# Temporary_Solution_v2.net
KiCad netlist of a schematic drawn in EAGLE
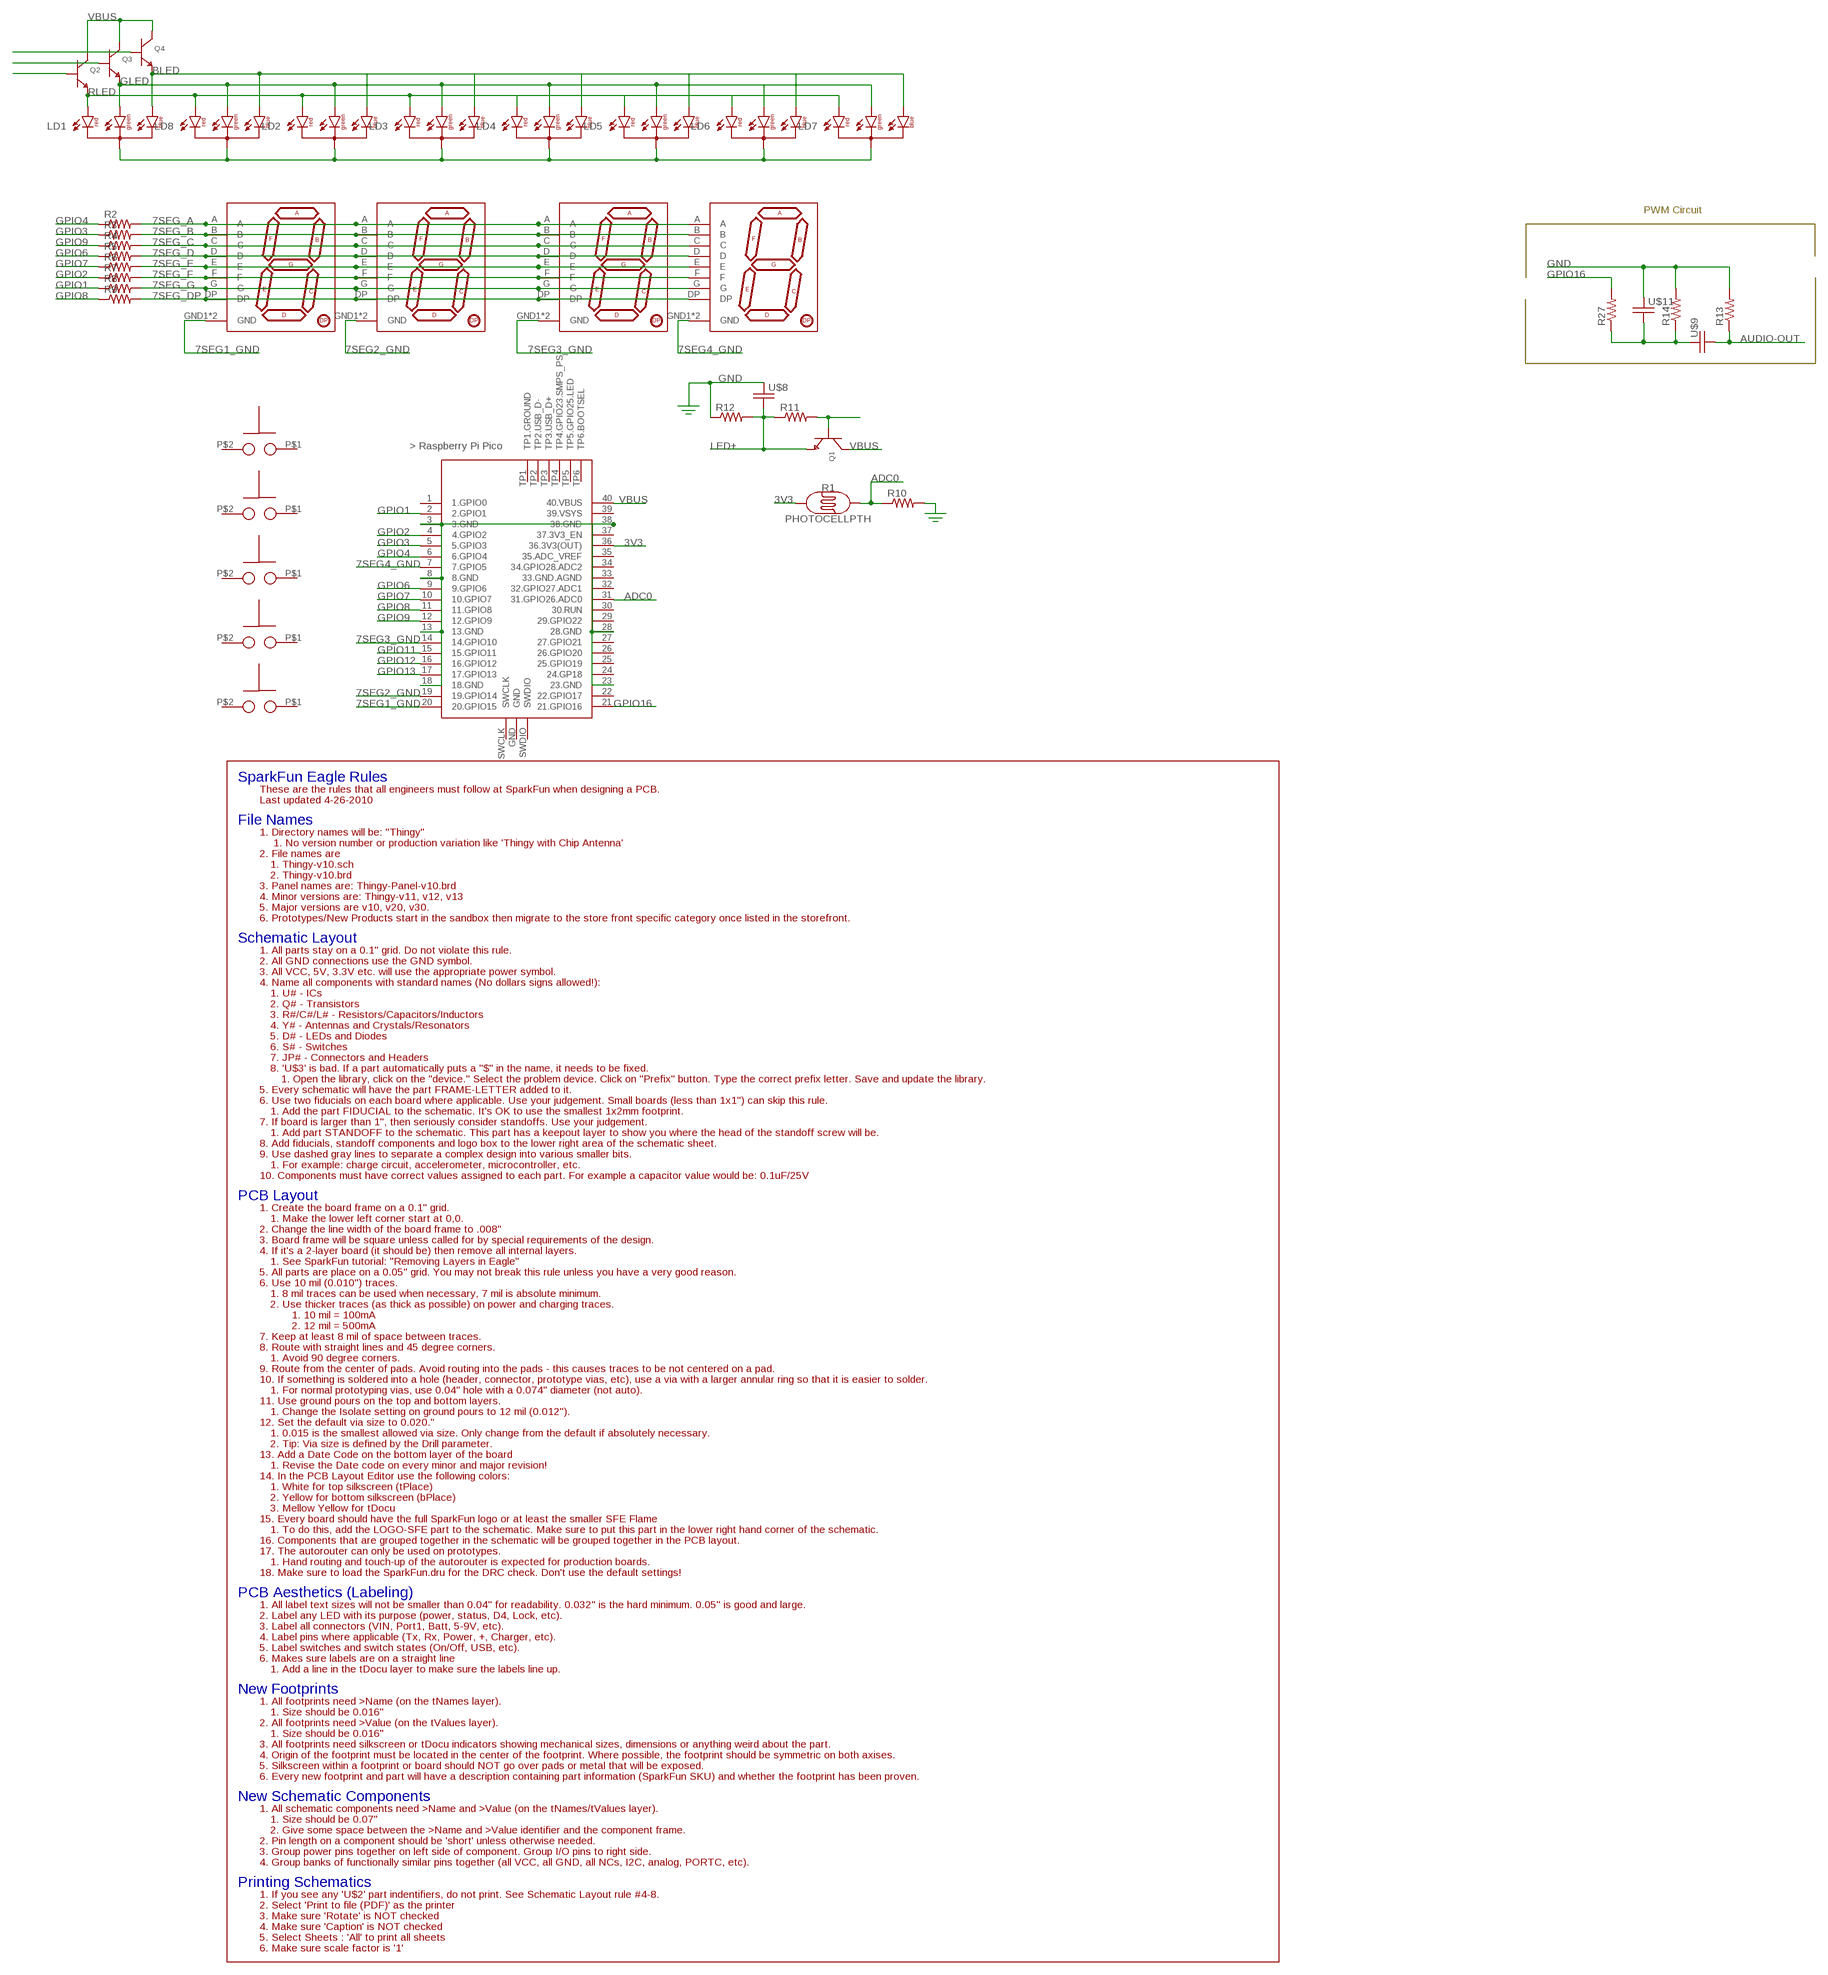
[diagram p0: schematic, sheet 1]

(export (version "E")
  (design (tool "Eeschema 10.0.6"))
  (components
    (comp (ref "D1")
      (value "7SEGMENT-1DIGIT")
      (footprint "eagle-import:7SEGMENT-1DIGIT")
      (libsource (lib "eagle-import") (part "7SEGMENT-1DIGIT"))
    )
    (comp (ref "D2")
      (value "7SEGMENT-1DIGIT")
      (footprint "eagle-import:7SEGMENT-1DIGIT")
      (libsource (lib "eagle-import") (part "7SEGMENT-1DIGIT"))
    )
    (comp (ref "D3")
      (value "7SEGMENT-1DIGIT")
      (footprint "eagle-import:7SEGMENT-1DIGIT")
      (libsource (lib "eagle-import") (part "7SEGMENT-1DIGIT"))
    )
    (comp (ref "D4")
      (value "7SEGMENT-1DIGIT")
      (footprint "eagle-import:7SEGMENT-1DIGIT")
      (libsource (lib "eagle-import") (part "7SEGMENT-1DIGIT"))
    )
    (comp (ref "LD1")
      (value "LED_RGB")
      (footprint "eagle-import:LED_RGB")
      (libsource (lib "eagle-import") (part "LED_RGB"))
    )
    (comp (ref "LD2")
      (value "LED_RGB")
      (footprint "eagle-import:LED_RGB")
      (libsource (lib "eagle-import") (part "LED_RGB"))
    )
    (comp (ref "LD3")
      (value "LED_RGB")
      (footprint "eagle-import:LED_RGB")
      (libsource (lib "eagle-import") (part "LED_RGB"))
    )
    (comp (ref "LD4")
      (value "LED_RGB")
      (footprint "eagle-import:LED_RGB")
      (libsource (lib "eagle-import") (part "LED_RGB"))
    )
    (comp (ref "LD5")
      (value "LED_RGB")
      (footprint "eagle-import:LED_RGB")
      (libsource (lib "eagle-import") (part "LED_RGB"))
    )
    (comp (ref "LD6")
      (value "LED_RGB")
      (footprint "eagle-import:LED_RGB")
      (libsource (lib "eagle-import") (part "LED_RGB"))
    )
    (comp (ref "LD7")
      (value "LED_RGB")
      (footprint "eagle-import:LED_RGB")
      (libsource (lib "eagle-import") (part "LED_RGB"))
    )
    (comp (ref "LD8")
      (value "LED_RGB")
      (footprint "eagle-import:LED_RGB")
      (libsource (lib "eagle-import") (part "LED_RGB"))
    )
    (comp (ref "Q1")
      (value "BJT_NPN_EBC_2N2222")
      (footprint "eagle-import:NPN_EBC_.1IN")
      (libsource (lib "eagle-import") (part "BJT_NPN_EBC_2N2222"))
    )
    (comp (ref "Q2")
      (value "BJT_NPN_EBC_2N2222")
      (footprint "eagle-import:NPN_EBC_.1IN")
      (libsource (lib "eagle-import") (part "BJT_NPN_EBC_2N2222"))
    )
    (comp (ref "Q3")
      (value "BJT_NPN_EBC_2N2222")
      (footprint "eagle-import:NPN_EBC_.1IN")
      (libsource (lib "eagle-import") (part "BJT_NPN_EBC_2N2222"))
    )
    (comp (ref "Q4")
      (value "BJT_NPN_EBC_2N2222")
      (footprint "eagle-import:NPN_EBC_.1IN")
      (libsource (lib "eagle-import") (part "BJT_NPN_EBC_2N2222"))
    )
    (comp (ref "R1")
      (value "PHOTOCELLPTH")
      (footprint "eagle-import:PHOTOCELL")
      (libsource (lib "eagle-import") (part "PHOTOCELLPTH"))
    )
    (comp (ref "R2")
      (value "R-US_0207/7")
      (footprint "eagle-import:0207_7")
      (libsource (lib "eagle-import") (part "R-US_0207/7"))
    )
    (comp (ref "R3")
      (value "R-US_0207/7")
      (footprint "eagle-import:0207_7")
      (libsource (lib "eagle-import") (part "R-US_0207/7"))
    )
    (comp (ref "R4")
      (value "R-US_0207/7")
      (footprint "eagle-import:0207_7")
      (libsource (lib "eagle-import") (part "R-US_0207/7"))
    )
    (comp (ref "R5")
      (value "R-US_0207/7")
      (footprint "eagle-import:0207_7")
      (libsource (lib "eagle-import") (part "R-US_0207/7"))
    )
    (comp (ref "R6")
      (value "R-US_0207/7")
      (footprint "eagle-import:0207_7")
      (libsource (lib "eagle-import") (part "R-US_0207/7"))
    )
    (comp (ref "R7")
      (value "R-US_0207/7")
      (footprint "eagle-import:0207_7")
      (libsource (lib "eagle-import") (part "R-US_0207/7"))
    )
    (comp (ref "R8")
      (value "R-US_0207/7")
      (footprint "eagle-import:0207_7")
      (libsource (lib "eagle-import") (part "R-US_0207/7"))
    )
    (comp (ref "R9")
      (value "R-US_0207/7")
      (footprint "eagle-import:0207_7")
      (libsource (lib "eagle-import") (part "R-US_0207/7"))
    )
    (comp (ref "R10")
      (value "R-US_0207/7")
      (footprint "eagle-import:0207_7")
      (libsource (lib "eagle-import") (part "R-US_0207/7"))
    )
    (comp (ref "R11")
      (value "R-US_0207/7")
      (footprint "eagle-import:0207_7")
      (libsource (lib "eagle-import") (part "R-US_0207/7"))
    )
    (comp (ref "R12")
      (value "R-US_0207/7")
      (footprint "eagle-import:0207_7")
      (libsource (lib "eagle-import") (part "R-US_0207/7"))
    )
    (comp (ref "R13")
      (value "R-US_0207/7")
      (footprint "eagle-import:0207_7")
      (libsource (lib "eagle-import") (part "R-US_0207/7"))
    )
    (comp (ref "R14")
      (value "R-US_0207/7")
      (footprint "eagle-import:0207_7")
      (libsource (lib "eagle-import") (part "R-US_0207/7"))
    )
    (comp (ref "R27")
      (value "R-US_0207/7")
      (footprint "eagle-import:0207_7")
      (libsource (lib "eagle-import") (part "R-US_0207/7"))
    )
    (comp (ref "U$2")
      (value "RASPBERRY_PI_PICO_TH")
      (footprint "eagle-import:RASPBERRY_PI_PICO_TH")
      (libsource (lib "eagle-import") (part "RASPBERRY_PI_PICO_TH"))
    )
    (comp (ref "U$3")
      (value "BUTTONPUSHBUTTON_2-PIN")
      (footprint "eagle-import:BUTTON_PUSHBUTTON_2-PIN")
      (libsource (lib "eagle-import") (part "BUTTONPUSHBUTTON_2-PIN"))
    )
    (comp (ref "U$4")
      (value "BUTTONPUSHBUTTON_2-PIN")
      (footprint "eagle-import:BUTTON_PUSHBUTTON_2-PIN")
      (libsource (lib "eagle-import") (part "BUTTONPUSHBUTTON_2-PIN"))
    )
    (comp (ref "U$5")
      (value "BUTTONPUSHBUTTON_2-PIN")
      (footprint "eagle-import:BUTTON_PUSHBUTTON_2-PIN")
      (libsource (lib "eagle-import") (part "BUTTONPUSHBUTTON_2-PIN"))
    )
    (comp (ref "U$6")
      (value "BUTTONPUSHBUTTON_2-PIN")
      (footprint "eagle-import:BUTTON_PUSHBUTTON_2-PIN")
      (libsource (lib "eagle-import") (part "BUTTONPUSHBUTTON_2-PIN"))
    )
    (comp (ref "U$7")
      (value "BUTTONPUSHBUTTON_2-PIN")
      (footprint "eagle-import:BUTTON_PUSHBUTTON_2-PIN")
      (libsource (lib "eagle-import") (part "BUTTONPUSHBUTTON_2-PIN"))
    )
    (comp (ref "U$8")
      (value "CAPACITOR-NONPOLARIZEDTH-CERAMIC")
      (footprint "eagle-import:CAPACITOR-CERAMIC")
      (libsource (lib "eagle-import") (part "CAPACITOR-NONPOLARIZEDTH-CERAMIC"))
    )
    (comp (ref "U$9")
      (value "CAPACITOR-NONPOLARIZEDTH-CERAMIC")
      (footprint "eagle-import:CAPACITOR-CERAMIC")
      (libsource (lib "eagle-import") (part "CAPACITOR-NONPOLARIZEDTH-CERAMIC"))
    )
    (comp (ref "U$11")
      (value "CAPACITOR-NONPOLARIZEDTH-CERAMIC")
      (footprint "eagle-import:CAPACITOR-CERAMIC")
      (libsource (lib "eagle-import") (part "CAPACITOR-NONPOLARIZEDTH-CERAMIC"))
    )
  )
  (nets
    (net (code "1") (name "/3V3") (class "Default")
      (node (ref "R1") (pin "1") (pinfunction "P$1_1") (pintype "bidirectional"))
      (node (ref "U$2") (pin "36") (pinfunction "36.3V3(OUT)_36") (pintype "bidirectional"))
    )
    (net (code "2") (name "/7SEG1_GND") (class "Default")
      (node (ref "D1") (pin "GND1") (pinfunction "GND_GND1") (pintype "bidirectional"))
      (node (ref "D1") (pin "GND2") (pinfunction "GND_GND2") (pintype "bidirectional"))
      (node (ref "U$2") (pin "20") (pinfunction "20.GPIO15_20") (pintype "bidirectional"))
    )
    (net (code "3") (name "/7SEG2_GND") (class "Default")
      (node (ref "D2") (pin "GND1") (pinfunction "GND_GND1") (pintype "bidirectional"))
      (node (ref "D2") (pin "GND2") (pinfunction "GND_GND2") (pintype "bidirectional"))
      (node (ref "U$2") (pin "19") (pinfunction "19.GPIO14_19") (pintype "bidirectional"))
    )
    (net (code "4") (name "/7SEG3_GND") (class "Default")
      (node (ref "D3") (pin "GND1") (pinfunction "GND_GND1") (pintype "bidirectional"))
      (node (ref "D3") (pin "GND2") (pinfunction "GND_GND2") (pintype "bidirectional"))
      (node (ref "U$2") (pin "14") (pinfunction "14.GPIO10_14") (pintype "bidirectional"))
    )
    (net (code "5") (name "/7SEG4_GND") (class "Default")
      (node (ref "D4") (pin "GND1") (pinfunction "GND_GND1") (pintype "bidirectional"))
      (node (ref "D4") (pin "GND2") (pinfunction "GND_GND2") (pintype "bidirectional"))
      (node (ref "U$2") (pin "7") (pinfunction "7.GPIO5_7") (pintype "bidirectional"))
    )
    (net (code "6") (name "/7SEG_A") (class "Default")
      (node (ref "D1") (pin "A") (pinfunction "A_A") (pintype "bidirectional"))
      (node (ref "D2") (pin "A") (pinfunction "A_A") (pintype "bidirectional"))
      (node (ref "D3") (pin "A") (pinfunction "A_A") (pintype "bidirectional"))
      (node (ref "D4") (pin "A") (pinfunction "A_A") (pintype "bidirectional"))
      (node (ref "R2") (pin "2") (pinfunction "2_2") (pintype "passive"))
    )
    (net (code "7") (name "/7SEG_B") (class "Default")
      (node (ref "D1") (pin "B") (pinfunction "B_B") (pintype "bidirectional"))
      (node (ref "D2") (pin "B") (pinfunction "B_B") (pintype "bidirectional"))
      (node (ref "D3") (pin "B") (pinfunction "B_B") (pintype "bidirectional"))
      (node (ref "D4") (pin "B") (pinfunction "B_B") (pintype "bidirectional"))
      (node (ref "R3") (pin "2") (pinfunction "2_2") (pintype "passive"))
    )
    (net (code "8") (name "/7SEG_C") (class "Default")
      (node (ref "D1") (pin "C") (pinfunction "C_C") (pintype "bidirectional"))
      (node (ref "D2") (pin "C") (pinfunction "C_C") (pintype "bidirectional"))
      (node (ref "D3") (pin "C") (pinfunction "C_C") (pintype "bidirectional"))
      (node (ref "D4") (pin "C") (pinfunction "C_C") (pintype "bidirectional"))
      (node (ref "R4") (pin "2") (pinfunction "2_2") (pintype "passive"))
    )
    (net (code "9") (name "/7SEG_D") (class "Default")
      (node (ref "D1") (pin "D") (pinfunction "D_D") (pintype "bidirectional"))
      (node (ref "D2") (pin "D") (pinfunction "D_D") (pintype "bidirectional"))
      (node (ref "D3") (pin "D") (pinfunction "D_D") (pintype "bidirectional"))
      (node (ref "D4") (pin "D") (pinfunction "D_D") (pintype "bidirectional"))
      (node (ref "R5") (pin "2") (pinfunction "2_2") (pintype "passive"))
    )
    (net (code "10") (name "/7SEG_DP") (class "Default")
      (node (ref "D1") (pin "DP") (pinfunction "DP_DP") (pintype "bidirectional"))
      (node (ref "D2") (pin "DP") (pinfunction "DP_DP") (pintype "bidirectional"))
      (node (ref "D3") (pin "DP") (pinfunction "DP_DP") (pintype "bidirectional"))
      (node (ref "D4") (pin "DP") (pinfunction "DP_DP") (pintype "bidirectional"))
      (node (ref "R9") (pin "2") (pinfunction "2_2") (pintype "passive"))
    )
    (net (code "11") (name "/7SEG_E") (class "Default")
      (node (ref "D1") (pin "E") (pinfunction "E_E") (pintype "bidirectional"))
      (node (ref "D2") (pin "E") (pinfunction "E_E") (pintype "bidirectional"))
      (node (ref "D3") (pin "E") (pinfunction "E_E") (pintype "bidirectional"))
      (node (ref "D4") (pin "E") (pinfunction "E_E") (pintype "bidirectional"))
      (node (ref "R6") (pin "2") (pinfunction "2_2") (pintype "passive"))
    )
    (net (code "12") (name "/7SEG_F") (class "Default")
      (node (ref "D1") (pin "F") (pinfunction "F_F") (pintype "bidirectional"))
      (node (ref "D2") (pin "F") (pinfunction "F_F") (pintype "bidirectional"))
      (node (ref "D3") (pin "F") (pinfunction "F_F") (pintype "bidirectional"))
      (node (ref "D4") (pin "F") (pinfunction "F_F") (pintype "bidirectional"))
      (node (ref "R7") (pin "2") (pinfunction "2_2") (pintype "passive"))
    )
    (net (code "13") (name "/7SEG_G") (class "Default")
      (node (ref "D1") (pin "G") (pinfunction "G_G") (pintype "bidirectional"))
      (node (ref "D2") (pin "G") (pinfunction "G_G") (pintype "bidirectional"))
      (node (ref "D3") (pin "G") (pinfunction "G_G") (pintype "bidirectional"))
      (node (ref "D4") (pin "G") (pinfunction "G_G") (pintype "bidirectional"))
      (node (ref "R8") (pin "2") (pinfunction "2_2") (pintype "passive"))
    )
    (net (code "14") (name "/ADC0") (class "Default")
      (node (ref "R1") (pin "2") (pinfunction "P$2_2") (pintype "bidirectional"))
      (node (ref "R10") (pin "1") (pinfunction "1_1") (pintype "passive"))
      (node (ref "U$2") (pin "31") (pinfunction "31.GPIO26.ADC0_31") (pintype "bidirectional"))
    )
    (net (code "15") (name "/AUDIO-OUT") (class "Default")
      (node (ref "R13") (pin "1") (pinfunction "1_1") (pintype "passive"))
      (node (ref "U$9") (pin "2") (pinfunction "2_2") (pintype "passive"))
    )
    (net (code "16") (name "/BLED") (class "Default")
      (node (ref "LD1") (pin "BLUE") (pinfunction "BLUE_BLUE") (pintype "passive"))
      (node (ref "LD2") (pin "BLUE") (pinfunction "BLUE_BLUE") (pintype "passive"))
      (node (ref "LD3") (pin "BLUE") (pinfunction "BLUE_BLUE") (pintype "passive"))
      (node (ref "LD4") (pin "BLUE") (pinfunction "BLUE_BLUE") (pintype "passive"))
      (node (ref "LD5") (pin "BLUE") (pinfunction "BLUE_BLUE") (pintype "passive"))
      (node (ref "LD6") (pin "BLUE") (pinfunction "BLUE_BLUE") (pintype "passive"))
      (node (ref "LD7") (pin "BLUE") (pinfunction "BLUE_BLUE") (pintype "passive"))
      (node (ref "LD8") (pin "BLUE") (pinfunction "BLUE_BLUE") (pintype "passive"))
      (node (ref "Q4") (pin "3") (pinfunction "E_3") (pintype "bidirectional"))
    )
    (net (code "17") (name "/GLED") (class "Default")
      (node (ref "LD1") (pin "GRN") (pinfunction "GREEN_GRN") (pintype "passive"))
      (node (ref "LD2") (pin "GRN") (pinfunction "GREEN_GRN") (pintype "passive"))
      (node (ref "LD3") (pin "GRN") (pinfunction "GREEN_GRN") (pintype "passive"))
      (node (ref "LD4") (pin "GRN") (pinfunction "GREEN_GRN") (pintype "passive"))
      (node (ref "LD5") (pin "GRN") (pinfunction "GREEN_GRN") (pintype "passive"))
      (node (ref "LD6") (pin "GRN") (pinfunction "GREEN_GRN") (pintype "passive"))
      (node (ref "LD7") (pin "GRN") (pinfunction "GREEN_GRN") (pintype "passive"))
      (node (ref "LD8") (pin "GRN") (pinfunction "GREEN_GRN") (pintype "passive"))
      (node (ref "Q3") (pin "3") (pinfunction "E_3") (pintype "bidirectional"))
    )
    (net (code "18") (name "/GND") (class "Default")
      (node (ref "R10") (pin "2") (pinfunction "2_2") (pintype "passive"))
      (node (ref "R12") (pin "1") (pinfunction "1_1") (pintype "passive"))
      (node (ref "R13") (pin "2") (pinfunction "2_2") (pintype "passive"))
      (node (ref "R14") (pin "2") (pinfunction "2_2") (pintype "passive"))
      (node (ref "U$11") (pin "1") (pinfunction "1_1") (pintype "passive"))
      (node (ref "U$2") (pin "13") (pinfunction "13.GND_13") (pintype "bidirectional"))
      (node (ref "U$2") (pin "18") (pinfunction "18.GND_18") (pintype "bidirectional"))
      (node (ref "U$2") (pin "23") (pinfunction "23.GND_23") (pintype "bidirectional"))
      (node (ref "U$2") (pin "28") (pinfunction "28.GND_28") (pintype "bidirectional"))
      (node (ref "U$2") (pin "3") (pinfunction "3.GND_3") (pintype "bidirectional"))
      (node (ref "U$2") (pin "38") (pinfunction "38.GND_38") (pintype "bidirectional"))
      (node (ref "U$2") (pin "8") (pinfunction "8.GND_8") (pintype "bidirectional"))
      (node (ref "U$8") (pin "1") (pinfunction "1_1") (pintype "passive"))
    )
    (net (code "19") (name "/GPIO1") (class "Default")
      (node (ref "R8") (pin "1") (pinfunction "1_1") (pintype "passive"))
      (node (ref "U$2") (pin "2") (pinfunction "2.GPIO1_2") (pintype "bidirectional"))
    )
    (net (code "20") (name "/GPIO2") (class "Default")
      (node (ref "R7") (pin "1") (pinfunction "1_1") (pintype "passive"))
      (node (ref "U$2") (pin "4") (pinfunction "4.GPIO2_4") (pintype "bidirectional"))
    )
    (net (code "21") (name "/GPIO3") (class "Default")
      (node (ref "R3") (pin "1") (pinfunction "1_1") (pintype "passive"))
      (node (ref "U$2") (pin "5") (pinfunction "5.GPIO3_5") (pintype "bidirectional"))
    )
    (net (code "22") (name "/GPIO4") (class "Default")
      (node (ref "R2") (pin "1") (pinfunction "1_1") (pintype "passive"))
      (node (ref "U$2") (pin "6") (pinfunction "6.GPIO4_6") (pintype "bidirectional"))
    )
    (net (code "23") (name "/GPIO6") (class "Default")
      (node (ref "R5") (pin "1") (pinfunction "1_1") (pintype "passive"))
      (node (ref "U$2") (pin "9") (pinfunction "9.GPIO6_9") (pintype "bidirectional"))
    )
    (net (code "24") (name "/GPIO7") (class "Default")
      (node (ref "R6") (pin "1") (pinfunction "1_1") (pintype "passive"))
      (node (ref "U$2") (pin "10") (pinfunction "10.GPIO7_10") (pintype "bidirectional"))
    )
    (net (code "25") (name "/GPIO8") (class "Default")
      (node (ref "R9") (pin "1") (pinfunction "1_1") (pintype "passive"))
      (node (ref "U$2") (pin "11") (pinfunction "11.GPIO8_11") (pintype "bidirectional"))
    )
    (net (code "26") (name "/GPIO9") (class "Default")
      (node (ref "R4") (pin "1") (pinfunction "1_1") (pintype "passive"))
      (node (ref "U$2") (pin "12") (pinfunction "12.GPIO9_12") (pintype "bidirectional"))
    )
    (net (code "27") (name "/GPIO11") (class "Default")
      (node (ref "U$2") (pin "15") (pinfunction "15.GPIO11_15") (pintype "bidirectional"))
    )
    (net (code "28") (name "/GPIO12") (class "Default")
      (node (ref "U$2") (pin "16") (pinfunction "16.GPIO12_16") (pintype "bidirectional"))
    )
    (net (code "29") (name "/GPIO13") (class "Default")
      (node (ref "U$2") (pin "17") (pinfunction "17.GPIO13_17") (pintype "bidirectional"))
    )
    (net (code "30") (name "/GPIO16") (class "Default")
      (node (ref "R27") (pin "2") (pinfunction "2_2") (pintype "passive"))
      (node (ref "U$2") (pin "21") (pinfunction "21.GPIO16_21") (pintype "bidirectional"))
    )
    (net (code "31") (name "/LED+") (class "Default")
      (node (ref "Q1") (pin "3") (pinfunction "E_3") (pintype "bidirectional"))
      (node (ref "R11") (pin "1") (pinfunction "1_1") (pintype "passive"))
      (node (ref "R12") (pin "2") (pinfunction "2_2") (pintype "passive"))
      (node (ref "U$8") (pin "2") (pinfunction "2_2") (pintype "passive"))
    )
    (net (code "32") (name "/RLED") (class "Default")
      (node (ref "LD1") (pin "RED") (pinfunction "RED_RED") (pintype "passive"))
      (node (ref "LD2") (pin "RED") (pinfunction "RED_RED") (pintype "passive"))
      (node (ref "LD3") (pin "RED") (pinfunction "RED_RED") (pintype "passive"))
      (node (ref "LD4") (pin "RED") (pinfunction "RED_RED") (pintype "passive"))
      (node (ref "LD5") (pin "RED") (pinfunction "RED_RED") (pintype "passive"))
      (node (ref "LD6") (pin "RED") (pinfunction "RED_RED") (pintype "passive"))
      (node (ref "LD7") (pin "RED") (pinfunction "RED_RED") (pintype "passive"))
      (node (ref "LD8") (pin "RED") (pinfunction "RED_RED") (pintype "passive"))
      (node (ref "Q2") (pin "3") (pinfunction "E_3") (pintype "bidirectional"))
    )
    (net (code "33") (name "/VBUS") (class "Default")
      (node (ref "Q1") (pin "2") (pinfunction "C_2") (pintype "bidirectional"))
      (node (ref "Q2") (pin "2") (pinfunction "C_2") (pintype "bidirectional"))
      (node (ref "Q3") (pin "2") (pinfunction "C_2") (pintype "bidirectional"))
      (node (ref "Q4") (pin "2") (pinfunction "C_2") (pintype "bidirectional"))
      (node (ref "U$2") (pin "40") (pinfunction "40.VBUS_40") (pintype "bidirectional"))
    )
    (net (code "34") (name "Net-(LD1-PadGND)") (class "Default")
      (node (ref "LD1") (pin "GND") (pinfunction "GND_GND") (pintype "passive"))
      (node (ref "LD2") (pin "GND") (pinfunction "GND_GND") (pintype "passive"))
      (node (ref "LD3") (pin "GND") (pinfunction "GND_GND") (pintype "passive"))
      (node (ref "LD4") (pin "GND") (pinfunction "GND_GND") (pintype "passive"))
      (node (ref "LD5") (pin "GND") (pinfunction "GND_GND") (pintype "passive"))
      (node (ref "LD6") (pin "GND") (pinfunction "GND_GND") (pintype "passive"))
      (node (ref "LD7") (pin "GND") (pinfunction "GND_GND") (pintype "passive"))
      (node (ref "LD8") (pin "GND") (pinfunction "GND_GND") (pintype "passive"))
    )
    (net (code "35") (name "Net-(Q1-B)") (class "Default")
      (node (ref "Q1") (pin "1") (pinfunction "B_1") (pintype "bidirectional"))
      (node (ref "R11") (pin "2") (pinfunction "2_2") (pintype "passive"))
    )
    (net (code "36") (name "Net-(R14-Pad1)") (class "Default")
      (node (ref "R14") (pin "1") (pinfunction "1_1") (pintype "passive"))
      (node (ref "R27") (pin "1") (pinfunction "1_1") (pintype "passive"))
      (node (ref "U$11") (pin "2") (pinfunction "2_2") (pintype "passive"))
      (node (ref "U$9") (pin "1") (pinfunction "1_1") (pintype "passive"))
    )
    (net (code "37") (name "unconnected-(Q2-B-Pad1)") (class "Default")
      (node (ref "Q2") (pin "1") (pinfunction "B_1") (pintype "bidirectional"))
    )
    (net (code "38") (name "unconnected-(Q3-B-Pad1)") (class "Default")
      (node (ref "Q3") (pin "1") (pinfunction "B_1") (pintype "bidirectional"))
    )
    (net (code "39") (name "unconnected-(Q4-B-Pad1)") (class "Default")
      (node (ref "Q4") (pin "1") (pinfunction "B_1") (pintype "bidirectional"))
    )
    (net (code "40") (name "unconnected-(U$2-1.GPIO0-Pad1)") (class "Default")
      (node (ref "U$2") (pin "1") (pinfunction "1.GPIO0_1") (pintype "bidirectional"))
    )
    (net (code "41") (name "unconnected-(U$2-22.GPIO17-Pad22)") (class "Default")
      (node (ref "U$2") (pin "22") (pinfunction "22.GPIO17_22") (pintype "bidirectional"))
    )
    (net (code "42") (name "unconnected-(U$2-24.GP18-Pad24)") (class "Default")
      (node (ref "U$2") (pin "24") (pinfunction "24.GP18_24") (pintype "bidirectional"))
    )
    (net (code "43") (name "unconnected-(U$2-25.GPIO19-Pad25)") (class "Default")
      (node (ref "U$2") (pin "25") (pinfunction "25.GPIO19_25") (pintype "bidirectional"))
    )
    (net (code "44") (name "unconnected-(U$2-26.GPIO20-Pad26)") (class "Default")
      (node (ref "U$2") (pin "26") (pinfunction "26.GPIO20_26") (pintype "bidirectional"))
    )
    (net (code "45") (name "unconnected-(U$2-27.GPIO21-Pad27)") (class "Default")
      (node (ref "U$2") (pin "27") (pinfunction "27.GPIO21_27") (pintype "bidirectional"))
    )
    (net (code "46") (name "unconnected-(U$2-29.GPIO22-Pad29)") (class "Default")
      (node (ref "U$2") (pin "29") (pinfunction "29.GPIO22_29") (pintype "bidirectional"))
    )
    (net (code "47") (name "unconnected-(U$2-30.RUN-Pad30)") (class "Default")
      (node (ref "U$2") (pin "30") (pinfunction "30.RUN_30") (pintype "bidirectional"))
    )
    (net (code "48") (name "unconnected-(U$2-32.GPIO27.ADC1-Pad32)") (class "Default")
      (node (ref "U$2") (pin "32") (pinfunction "32.GPIO27.ADC1_32") (pintype "bidirectional"))
    )
    (net (code "49") (name "unconnected-(U$2-33.GND.AGND-Pad33)") (class "Default")
      (node (ref "U$2") (pin "33") (pinfunction "33.GND.AGND_33") (pintype "bidirectional"))
    )
    (net (code "50") (name "unconnected-(U$2-34.GPIO28.ADC2-Pad34)") (class "Default")
      (node (ref "U$2") (pin "34") (pinfunction "34.GPIO28.ADC2_34") (pintype "bidirectional"))
    )
    (net (code "51") (name "unconnected-(U$2-35.ADC_VREF-Pad35)") (class "Default")
      (node (ref "U$2") (pin "35") (pinfunction "35.ADC_VREF_35") (pintype "bidirectional"))
    )
    (net (code "52") (name "unconnected-(U$2-37.3V3_EN-Pad37)") (class "Default")
      (node (ref "U$2") (pin "37") (pinfunction "37.3V3_EN_37") (pintype "bidirectional"))
    )
    (net (code "53") (name "unconnected-(U$2-39.VSYS-Pad39)") (class "Default")
      (node (ref "U$2") (pin "39") (pinfunction "39.VSYS_39") (pintype "bidirectional"))
    )
    (net (code "54") (name "unconnected-(U$2-PadGND)") (class "Default")
      (node (ref "U$2") (pin "GND") (pinfunction "GND_GND") (pintype "bidirectional"))
    )
    (net (code "55") (name "unconnected-(U$2-PadSWCLK)") (class "Default")
      (node (ref "U$2") (pin "SWCLK") (pinfunction "SWCLK_SWCLK") (pintype "bidirectional"))
    )
    (net (code "56") (name "unconnected-(U$2-PadSWDIO)") (class "Default")
      (node (ref "U$2") (pin "SWDIO") (pinfunction "SWDIO_SWDIO") (pintype "bidirectional"))
    )
    (net (code "57") (name "unconnected-(U$2-TP1.GROUND-PadTP1)") (class "Default")
      (node (ref "U$2") (pin "TP1") (pinfunction "TP1.GROUND_TP1") (pintype "bidirectional"))
    )
    (net (code "58") (name "unconnected-(U$2-TP2.USB_D--PadTP2)") (class "Default")
      (node (ref "U$2") (pin "TP2") (pinfunction "TP2.USB_D-_TP2") (pintype "bidirectional"))
    )
    (net (code "59") (name "unconnected-(U$2-TP3.USB_D+-PadTP3)") (class "Default")
      (node (ref "U$2") (pin "TP3") (pinfunction "TP3.USB_D+_TP3") (pintype "bidirectional"))
    )
    (net (code "60") (name "unconnected-(U$2-TP4.GPIO23.SMPS_PS-PadTP4)") (class "Default")
      (node (ref "U$2") (pin "TP4") (pinfunction "TP4.GPIO23.SMPS_PS_TP4") (pintype "bidirectional"))
    )
    (net (code "61") (name "unconnected-(U$2-TP5.GPIO25.LED-PadTP5)") (class "Default")
      (node (ref "U$2") (pin "TP5") (pinfunction "TP5.GPIO25.LED_TP5") (pintype "bidirectional"))
    )
    (net (code "62") (name "unconnected-(U$2-TP6.BOOTSEL-PadTP6)") (class "Default")
      (node (ref "U$2") (pin "TP6") (pinfunction "TP6.BOOTSEL_TP6") (pintype "bidirectional"))
    )
    (net (code "63") (name "unconnected-(U$3-PadP$1)") (class "Default")
      (node (ref "U$3") (pin "P$1") (pinfunction "P$1_P$1") (pintype "passive"))
    )
    (net (code "64") (name "unconnected-(U$3-PadP$2)") (class "Default")
      (node (ref "U$3") (pin "P$2") (pinfunction "P$2_P$2") (pintype "passive"))
    )
    (net (code "65") (name "unconnected-(U$4-PadP$1)") (class "Default")
      (node (ref "U$4") (pin "P$1") (pinfunction "P$1_P$1") (pintype "passive"))
    )
    (net (code "66") (name "unconnected-(U$4-PadP$2)") (class "Default")
      (node (ref "U$4") (pin "P$2") (pinfunction "P$2_P$2") (pintype "passive"))
    )
    (net (code "67") (name "unconnected-(U$5-PadP$1)") (class "Default")
      (node (ref "U$5") (pin "P$1") (pinfunction "P$1_P$1") (pintype "passive"))
    )
    (net (code "68") (name "unconnected-(U$5-PadP$2)") (class "Default")
      (node (ref "U$5") (pin "P$2") (pinfunction "P$2_P$2") (pintype "passive"))
    )
    (net (code "69") (name "unconnected-(U$6-PadP$1)") (class "Default")
      (node (ref "U$6") (pin "P$1") (pinfunction "P$1_P$1") (pintype "passive"))
    )
    (net (code "70") (name "unconnected-(U$6-PadP$2)") (class "Default")
      (node (ref "U$6") (pin "P$2") (pinfunction "P$2_P$2") (pintype "passive"))
    )
    (net (code "71") (name "unconnected-(U$7-PadP$1)") (class "Default")
      (node (ref "U$7") (pin "P$1") (pinfunction "P$1_P$1") (pintype "passive"))
    )
    (net (code "72") (name "unconnected-(U$7-PadP$2)") (class "Default")
      (node (ref "U$7") (pin "P$2") (pinfunction "P$2_P$2") (pintype "passive"))
    )
  )
)
